# micph.net
KiCad netlist of a schematic drawn in Altium Designer
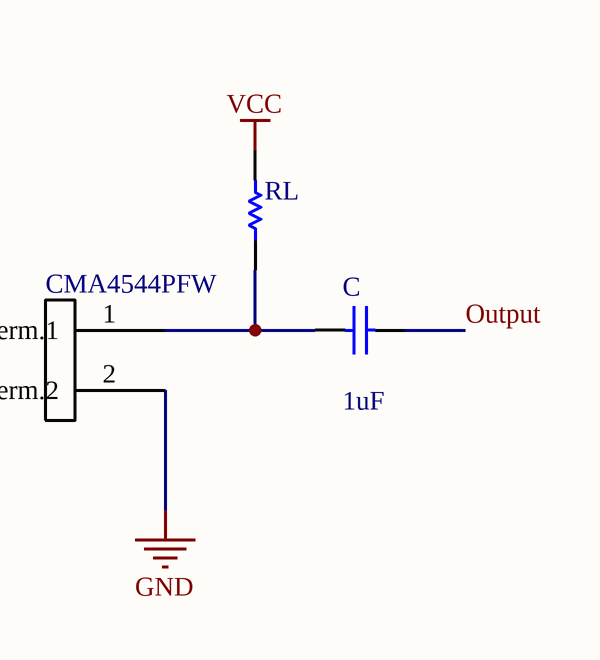
[diagram p0: micph.SchDoc]

(export (version "E")
  (design (tool "Eeschema 10.0.6"))
  (components
    (comp (ref "C")
      (value "1uF")
      (footprint "RAD-0.3")
      (description "Capacitor")
      (fields (field (name "PUBLISHER") "Altium Limited"))
      (libsource (lib "Miscellaneous Devices") (part "Cap"))
    )
    (comp (ref "CMA4544PFW") (value "~") (libsource (lib "microphone") (part "Component_1")))
    (comp (ref "RL")
      (value "~")
      (footprint "AXIAL-0.3")
      (description "Resistor")
      (fields (field (name "PUBLISHER") "Altium Limited"))
      (libsource (lib "Miscellaneous Devices") (part "Res1"))
    )
  )
  (nets
    (net (code "1") (name "/Output") (class "Default")
      (node (ref "C") (pin "2") (pinfunction "2_2") (pintype "passive"))
    )
    (net (code "2") (name "GND") (class "Default")
      (node (ref "CMA4544PFW") (pin "2") (pinfunction "Term.2_2") (pintype "passive"))
    )
    (net (code "3") (name "Net-(CMA4544PFW-Term.1)") (class "Default")
      (node (ref "C") (pin "1") (pinfunction "1_1") (pintype "passive"))
      (node (ref "CMA4544PFW") (pin "1") (pinfunction "Term.1_1") (pintype "passive"))
      (node (ref "RL") (pin "1") (pinfunction "1_1") (pintype "passive"))
    )
    (net (code "4") (name "VCC") (class "Default")
      (node (ref "RL") (pin "2") (pinfunction "2_2") (pintype "passive"))
    )
  )
)
